# -__12.net
KiCad netlist of a schematic drawn in Altium Designer
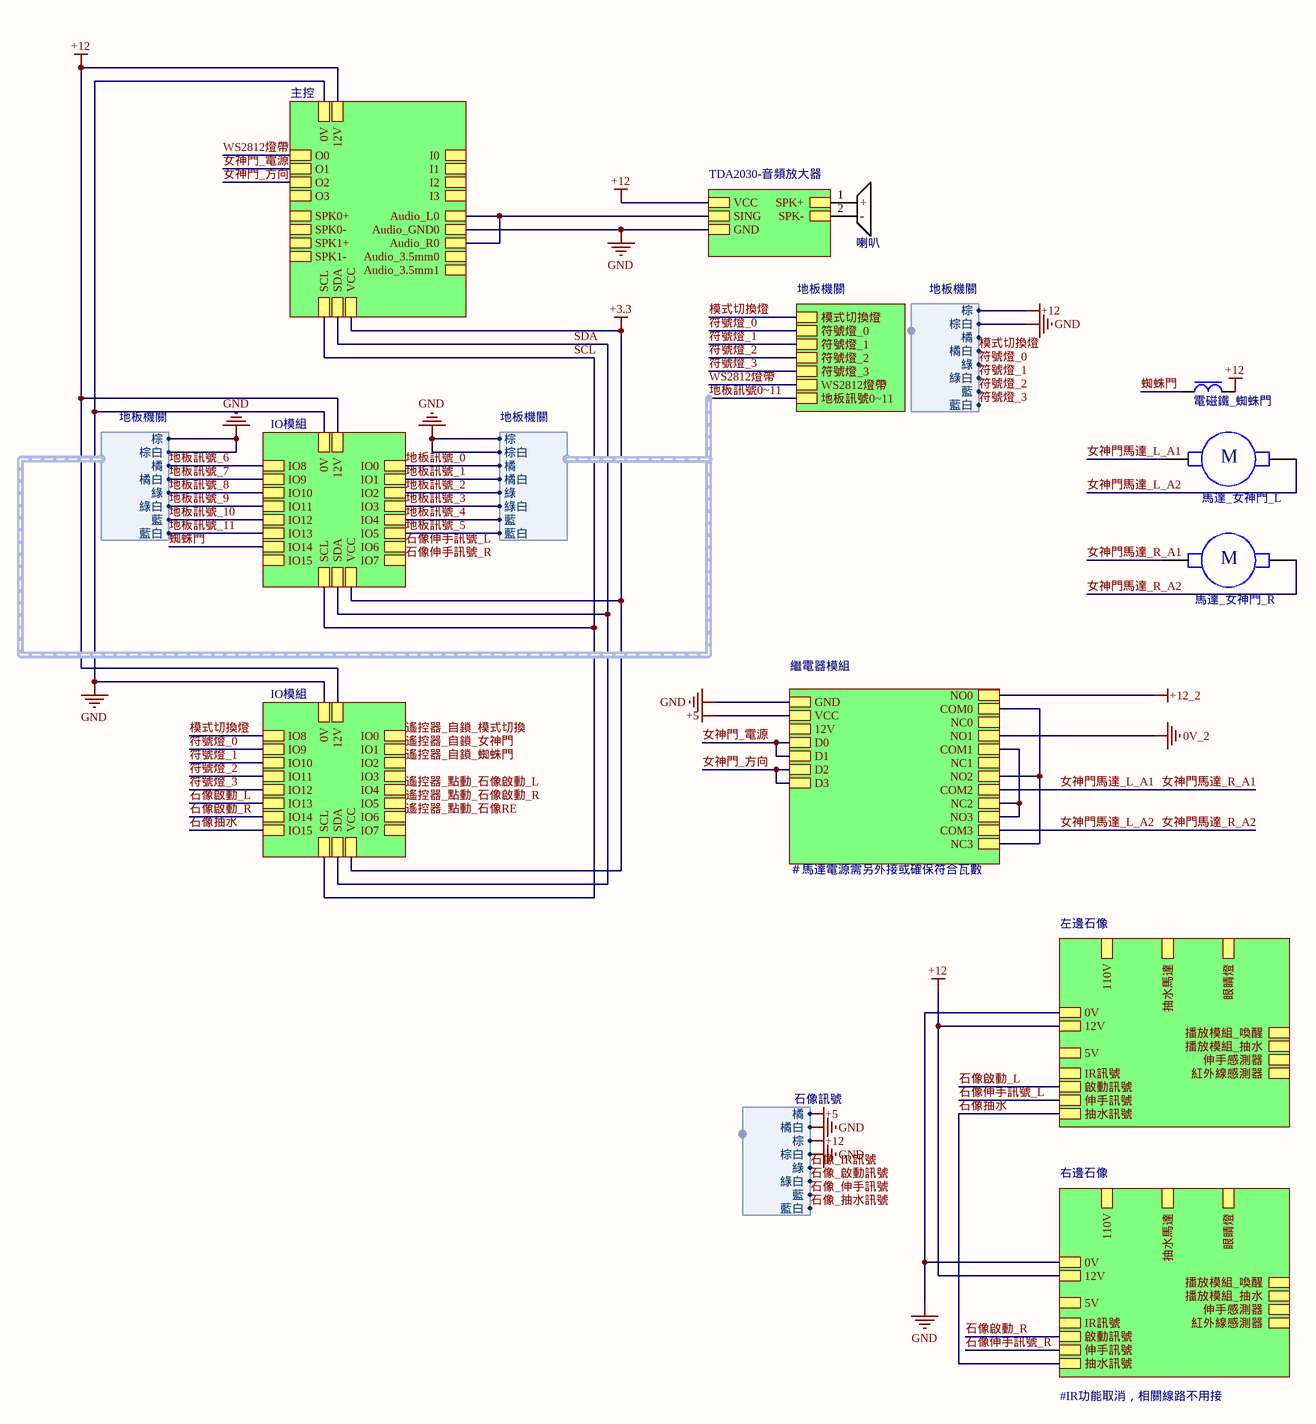
[diagram p0: 行天宮-流亡暗道_12符號地板機關.SchDoc]

(export (version "E")
  (design (tool "Eeschema 10.0.6"))
  (components
    (comp (ref "B9")
      (value "喇叭")
      (footprint "Buzzer_12085")
      (description "無源蜂鳴器")
      (libsource (lib "MyLibray") (part "Buzzer"))
    )
    (comp (ref "I6")
      (value "電磁鐵_蜘蛛門")
      (footprint "Inductor-0420")
      (description "一體成型電感")
      (libsource (lib "MyLibray") (part "Inductor"))
    )
    (comp (ref "MD1") (value "馬達_女神門_L") (description "直流馬達") (libsource (lib "電機圖塊") (part "Motor_DC")))
    (comp (ref "MD2") (value "馬達_女神門_R") (description "直流馬達") (libsource (lib "電機圖塊") (part "Motor_DC")))
  )
  (nets
    (net (code "4") (name "+12") (class "Default")
      (node (ref "I6") (pin "2") (pinfunction "2_2") (pintype "passive"))
    )
    (net (code "30") (name "/SPK+") (class "Default")
      (node (ref "B9") (pin "1") (pinfunction "+_1") (pintype "passive"))
    )
    (net (code "31") (name "/SPK-") (class "Default")
      (node (ref "B9") (pin "2") (pinfunction "-_2") (pintype "passive"))
    )
    (net (code "54") (name "/女神門馬達_L_A1") (class "Default")
      (node (ref "MD1") (pin "4") (pinfunction "4_4") (pintype "power_in"))
      (node (ref "MD2") (pin "4") (pinfunction "4_4") (pintype "power_in"))
    )
    (net (code "55") (name "/女神門馬達_L_A2") (class "Default")
      (node (ref "MD1") (pin "4") (pinfunction "4_4") (pintype "power_in"))
      (node (ref "MD2") (pin "4") (pinfunction "4_4") (pintype "power_in"))
    )
    (net (code "80") (name "/蜘蛛門") (class "Default")
      (node (ref "I6") (pin "1") (pinfunction "1_1") (pintype "passive"))
    )
  )
)
